# Motor_driver.net
KiCad netlist of a schematic drawn in Altium Designer
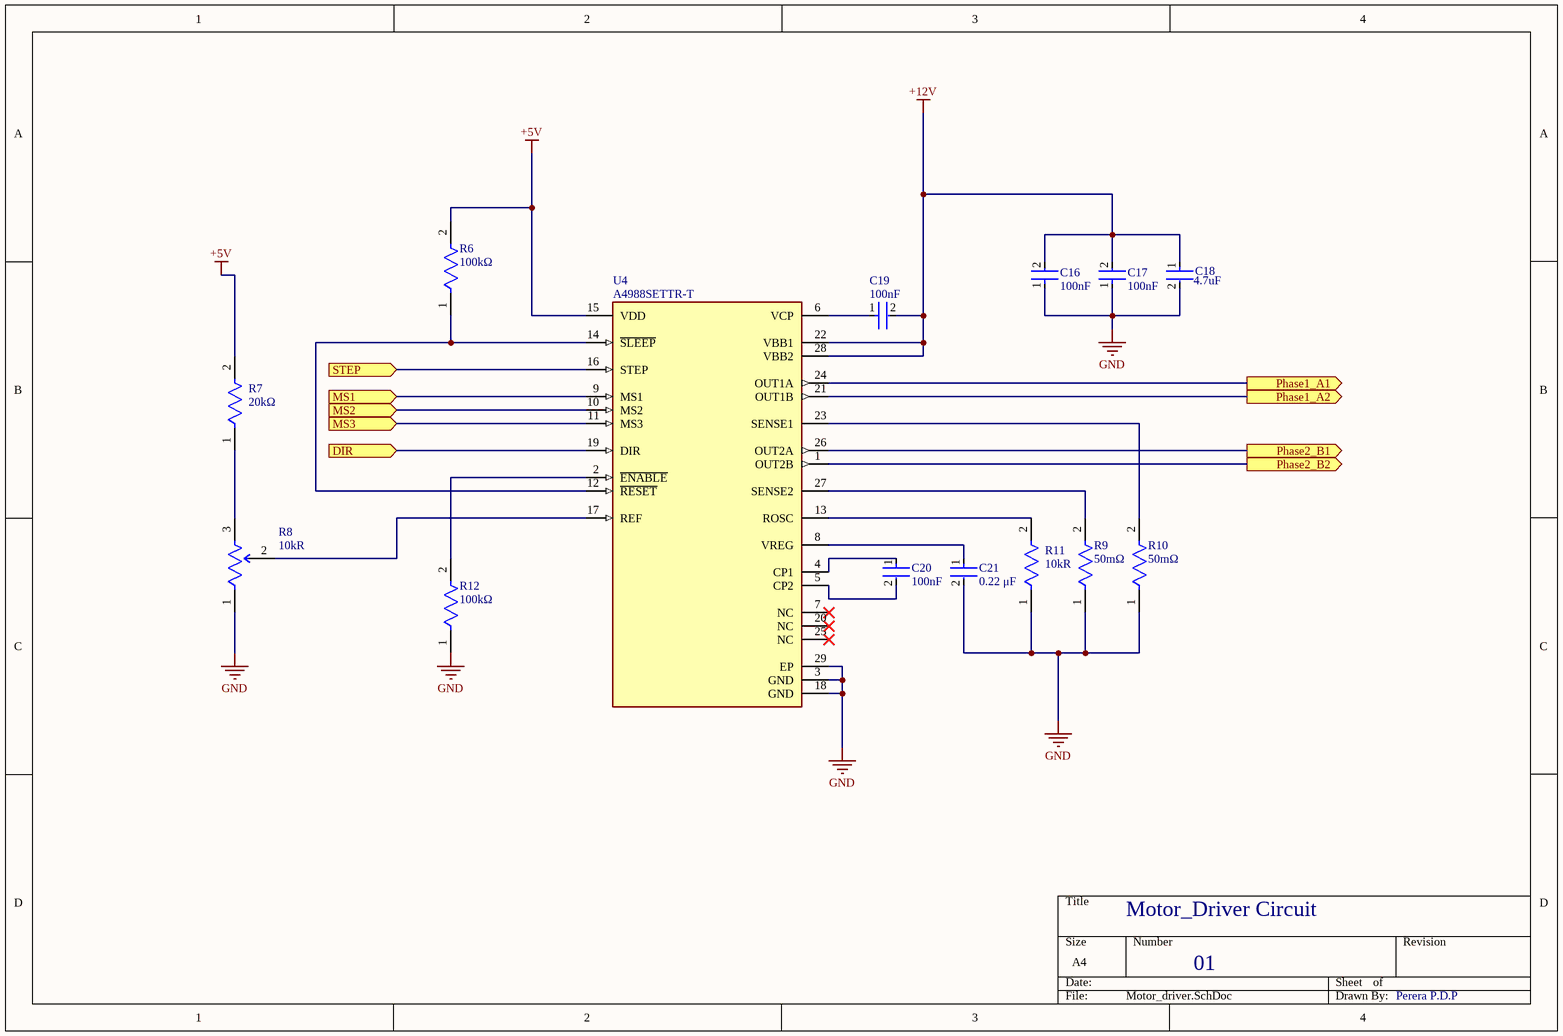
[diagram p0: Motor_driver.SchDoc]

(export (version "E")
  (design (tool "Eeschema 10.0.6"))
  (components
    (comp (ref "C16")
      (value "08055C104KAT2A")
      (footprint "FP-0805-L_2_01_0_2-W_1_25-IPC_C")
      (description "General Purpose Ceramic Capacitor, 0805, 100nF, 10%, X7R, 0.15, 50V")
      (fields
        (field (name "TOLERANCE") "10%")
        (field (name "VOLTAGE") "50V")
        (field (name "CAPACITANCE") "100nF")
      )
      (libsource (lib "Altium Content Vault") (part "02cd4be3c70576c341d710602a673aa"))
    )
    (comp (ref "C17")
      (value "08055C104KAT2A")
      (footprint "FP-0805-L_2_01_0_2-W_1_25-IPC_C")
      (description "General Purpose Ceramic Capacitor, 0805, 100nF, 10%, X7R, 0.15, 50V")
      (fields
        (field (name "TOLERANCE") "10%")
        (field (name "VOLTAGE") "50V")
        (field (name "CAPACITANCE") "100nF")
      )
      (libsource (lib "Altium Content Vault") (part "02cd4be3c70576c341d710602a673aa"))
    )
    (comp (ref "C18")
      (value "0805YC475KAT2A")
      (footprint "FP-0805-L_2_01_0_2-W_1_25-MFG")
      (description "General Purpose Ceramic Capacitor, 0805, 4.7uF, 10%, X7R, 15%, 16V")
      (fields
        (field (name "VOLTAGE") "10V")
        (field (name "TOLERANCE") "10%")
        (field (name "CAPACITANCE") "4.7uF")
      )
      (libsource (lib "Altium Content Vault") (part "02cd4be3c70576c341d710602a673aa"))
    )
    (comp (ref "C19")
      (value "08055C104KAT2A")
      (footprint "FP-0805-L_2_01_0_2-W_1_25-IPC_C")
      (description "General Purpose Ceramic Capacitor, 0805, 100nF, 10%, X7R, 0.15, 50V")
      (fields
        (field (name "TOLERANCE") "10%")
        (field (name "VOLTAGE") "50V")
        (field (name "CAPACITANCE") "100nF")
      )
      (libsource (lib "Altium Content Vault") (part "02cd4be3c70576c341d710602a673aa"))
    )
    (comp (ref "C20")
      (value "08055C104KAT2A")
      (footprint "FP-0805-L_2_01_0_2-W_1_25-IPC_C")
      (description "General Purpose Ceramic Capacitor, 0805, 100nF, 10%, X7R, 0.15, 50V")
      (fields
        (field (name "TOLERANCE") "10%")
        (field (name "VOLTAGE") "50V")
        (field (name "CAPACITANCE") "100nF")
      )
      (libsource (lib "Altium Content Vault") (part "02cd4be3c70576c341d710602a673aa"))
    )
    (comp (ref "C21")
      (value "0.22 μF")
      (footprint "FP-C0805C-DN-MFG")
      (description "CAP CER 0.22UF 50V X7R 0805")
      (fields
        (field (name "MANUFACTURER") "KEMET")
        (field (name "OCTOPART") "https://octopart.com/c0805c224k5ractu-kemet-144670")
      )
      (libsource (lib "Altium Content Vault") (part "b4654b650e69147ec39a6b967a45e02"))
    )
    (comp (ref "R6")
      (value "RC0805FR-07100KL")
      (footprint "FP-RC0805-0_6-IPC_C")
      (description "RES 100K OHM 1% 1/8W 0805")
      (fields (field (name "TOLERANCE") "1%") (field (name "RESISTANCE") "100kΩ"))
      (libsource (lib "Altium Content Vault") (part "1029c3af85768c4190bb7ad29bc67b5"))
    )
    (comp (ref "R7")
      (value "ERA6AEB203V")
      (footprint "FP-ERA6A-MFG")
      (description "RES 20K OHM 0.1% 1/8W 0805")
      (fields (field (name "TOLERANCE") "0.1%") (field (name "RESISTANCE") "20kΩ"))
      (libsource (lib "Altium Content Vault") (part "1029c3af85768c4190bb7ad29bc67b5"))
    )
    (comp (ref "R8")
      (value "3361P-1-103GLF")
      (footprint "FP-3361P-MFG")
      (description "TRIMMER 10K OHM 0.5W GW TOP ADJ")
      (fields (field (name "TOLERANCE") "10%") (field (name "RESISTANCE") "10kR"))
      (libsource (lib "Altium Content Vault") (part "2dcfd2547301a7d3209a5e99acfd772"))
    )
    (comp (ref "R9")
      (value "WSL2512R0500FEA")
      (footprint "FP-WSL2512-MFG")
      (description "RES 0.05 OHM 1% 1W 2512")
      (fields
        (field (name "TOLERANCE") "1%")
        (field (name "RESISTANCE") "50mΩ")
        (field (name "OCTOPART") "https://octopart.com/wsl2512r0500fea-vishay-39744678")
      )
      (libsource (lib "Altium Content Vault") (part "1029c3af85768c4190bb7ad29bc67b5"))
    )
    (comp (ref "R10")
      (value "WSL2512R0500FEA")
      (footprint "FP-WSL2512-MFG")
      (description "RES 0.05 OHM 1% 1W 2512")
      (fields
        (field (name "TOLERANCE") "1%")
        (field (name "RESISTANCE") "50mΩ")
        (field (name "OCTOPART") "https://octopart.com/wsl2512r0500fea-vishay-39744678")
      )
      (libsource (lib "Altium Content Vault") (part "1029c3af85768c4190bb7ad29bc67b5"))
    )
    (comp (ref "R11")
      (value "CRCW080510K0FKEA")
      (footprint "FP-CRCW0805-e3-IPC_A")
      (description "RES Thick Film, 10kΩ, 1%, 0.125W, 100ppm/°C, 0805")
      (fields (field (name "RESISTANCE") "10kR") (field (name "TOLERANCE") "1%"))
      (libsource (lib "Altium Content Vault") (part "1029c3af85768c4190bb7ad29bc67b5"))
    )
    (comp (ref "R12")
      (value "RC0805FR-07100KL")
      (footprint "FP-RC0805-0_6-IPC_C")
      (description "RES 100K OHM 1% 1/8W 0805")
      (fields (field (name "TOLERANCE") "1%") (field (name "RESISTANCE") "100kΩ"))
      (libsource (lib "Altium Content Vault") (part "1029c3af85768c4190bb7ad29bc67b5"))
    )
    (comp (ref "U4")
      (value "A4988SETTR-T")
      (footprint "FP-ET-28-MFG")
      (description "IC MTR DRVR BIPOLAR 3-5.5V 28QFN")
      (libsource (lib "Altium Content Vault") (part "7d8f66b9ff4f6e67aa26ce86ffb8e2d"))
    )
  )
  (nets
    (net (code "1") (name "+5V") (class "Default")
      (node (ref "R6") (pin "2") (pinfunction "2_2") (pintype "passive"))
      (node (ref "R7") (pin "2") (pinfunction "2_2") (pintype "passive"))
      (node (ref "U4") (pin "15") (pinfunction "VDD_15") (pintype "power_in"))
    )
    (net (code "2") (name "+12V") (class "Default")
      (node (ref "C16") (pin "2") (pinfunction "2_2") (pintype "passive"))
      (node (ref "C17") (pin "2") (pinfunction "2_2") (pintype "passive"))
      (node (ref "C18") (pin "1") (pinfunction "1_1") (pintype "passive"))
      (node (ref "C19") (pin "2") (pinfunction "2_2") (pintype "passive"))
      (node (ref "U4") (pin "22") (pinfunction "VBB1_22") (pintype "power_in"))
      (node (ref "U4") (pin "28") (pinfunction "VBB2_28") (pintype "power_in"))
    )
    (net (code "3") (name "/DIR") (class "Default")
      (node (ref "U4") (pin "19") (pinfunction "DIR_19") (pintype "input"))
    )
    (net (code "4") (name "/MS1") (class "Default")
      (node (ref "U4") (pin "9") (pinfunction "MS1_9") (pintype "input"))
    )
    (net (code "5") (name "/MS2") (class "Default")
      (node (ref "U4") (pin "10") (pinfunction "MS2_10") (pintype "input"))
    )
    (net (code "6") (name "/MS3") (class "Default")
      (node (ref "U4") (pin "11") (pinfunction "MS3_11") (pintype "input"))
    )
    (net (code "7") (name "/Phase1_A1") (class "Default")
      (node (ref "U4") (pin "24") (pinfunction "OUT1A_24") (pintype "output"))
    )
    (net (code "8") (name "/Phase1_A2") (class "Default")
      (node (ref "U4") (pin "21") (pinfunction "OUT1B_21") (pintype "output"))
    )
    (net (code "9") (name "/Phase2_B1") (class "Default")
      (node (ref "U4") (pin "26") (pinfunction "OUT2A_26") (pintype "output"))
    )
    (net (code "10") (name "/Phase2_B2") (class "Default")
      (node (ref "U4") (pin "1") (pinfunction "OUT2B_1") (pintype "output"))
    )
    (net (code "11") (name "/STEP") (class "Default")
      (node (ref "U4") (pin "16") (pinfunction "STEP_16") (pintype "input"))
    )
    (net (code "12") (name "GND") (class "Default")
      (node (ref "C16") (pin "1") (pinfunction "1_1") (pintype "passive"))
      (node (ref "C17") (pin "1") (pinfunction "1_1") (pintype "passive"))
      (node (ref "C18") (pin "2") (pinfunction "2_2") (pintype "passive"))
      (node (ref "C21") (pin "2") (pinfunction "2_2") (pintype "passive"))
      (node (ref "R10") (pin "1") (pinfunction "1_1") (pintype "passive"))
      (node (ref "R11") (pin "1") (pinfunction "1_1") (pintype "passive"))
      (node (ref "R12") (pin "1") (pinfunction "1_1") (pintype "passive"))
      (node (ref "R8") (pin "1") (pinfunction "CCW_1") (pintype "passive"))
      (node (ref "R9") (pin "1") (pinfunction "1_1") (pintype "passive"))
      (node (ref "U4") (pin "18") (pinfunction "GND_18") (pintype "power_in"))
      (node (ref "U4") (pin "29") (pinfunction "EP_29") (pintype "power_in"))
      (node (ref "U4") (pin "3") (pinfunction "GND_3") (pintype "power_in"))
    )
    (net (code "13") (name "Net-(R8-CW)") (class "Default")
      (node (ref "R7") (pin "1") (pinfunction "1_1") (pintype "passive"))
      (node (ref "R8") (pin "3") (pinfunction "CW_3") (pintype "passive"))
    )
    (net (code "14") (name "Net-(R8-WIPER)") (class "Default")
      (node (ref "R8") (pin "2") (pinfunction "WIPER_2") (pintype "passive"))
      (node (ref "U4") (pin "17") (pinfunction "REF_17") (pintype "input"))
    )
    (net (code "15") (name "Net-(U4-CP1)") (class "Default")
      (node (ref "C20") (pin "1") (pinfunction "1_1") (pintype "passive"))
      (node (ref "U4") (pin "4") (pinfunction "CP1_4") (pintype "passive"))
    )
    (net (code "16") (name "Net-(U4-CP2)") (class "Default")
      (node (ref "C20") (pin "2") (pinfunction "2_2") (pintype "passive"))
      (node (ref "U4") (pin "5") (pinfunction "CP2_5") (pintype "passive"))
    )
    (net (code "17") (name "Net-(U4-ROSC)") (class "Default")
      (node (ref "R11") (pin "2") (pinfunction "2_2") (pintype "passive"))
      (node (ref "U4") (pin "13") (pinfunction "ROSC_13") (pintype "passive"))
    )
    (net (code "18") (name "Net-(U4-SENSE1)") (class "Default")
      (node (ref "R10") (pin "2") (pinfunction "2_2") (pintype "passive"))
      (node (ref "U4") (pin "23") (pinfunction "SENSE1_23") (pintype "passive"))
    )
    (net (code "19") (name "Net-(U4-SENSE2)") (class "Default")
      (node (ref "R9") (pin "2") (pinfunction "2_2") (pintype "passive"))
      (node (ref "U4") (pin "27") (pinfunction "SENSE2_27") (pintype "passive"))
    )
    (net (code "20") (name "Net-(U4-VCP)") (class "Default")
      (node (ref "C19") (pin "1") (pinfunction "1_1") (pintype "passive"))
      (node (ref "U4") (pin "6") (pinfunction "VCP_6") (pintype "passive"))
    )
    (net (code "21") (name "Net-(U4-VREG)") (class "Default")
      (node (ref "C21") (pin "1") (pinfunction "1_1") (pintype "passive"))
      (node (ref "U4") (pin "8") (pinfunction "VREG_8") (pintype "passive"))
    )
    (net (code "22") (name "Net-(U4-~{ENABLE})") (class "Default")
      (node (ref "R12") (pin "2") (pinfunction "2_2") (pintype "passive"))
      (node (ref "U4") (pin "2") (pinfunction "~{ENABLE}_2") (pintype "input"))
    )
    (net (code "23") (name "Net-(U4-~{RESET})") (class "Default")
      (node (ref "R6") (pin "1") (pinfunction "1_1") (pintype "passive"))
      (node (ref "U4") (pin "12") (pinfunction "~{RESET}_12") (pintype "input"))
      (node (ref "U4") (pin "14") (pinfunction "~{SLEEP}_14") (pintype "input"))
    )
    (net (code "24") (name "unconnected-(U4-NC-Pad7)") (class "Default")
      (node (ref "U4") (pin "7") (pinfunction "NC_7") (pintype "passive+no_connect"))
    )
    (net (code "25") (name "unconnected-(U4-NC-Pad20)") (class "Default")
      (node (ref "U4") (pin "20") (pinfunction "NC_20") (pintype "passive+no_connect"))
    )
    (net (code "26") (name "unconnected-(U4-NC-Pad25)") (class "Default")
      (node (ref "U4") (pin "25") (pinfunction "NC_25") (pintype "passive+no_connect"))
    )
  )
)
